# trill-square.net
KiCad netlist of a schematic drawn in EAGLE
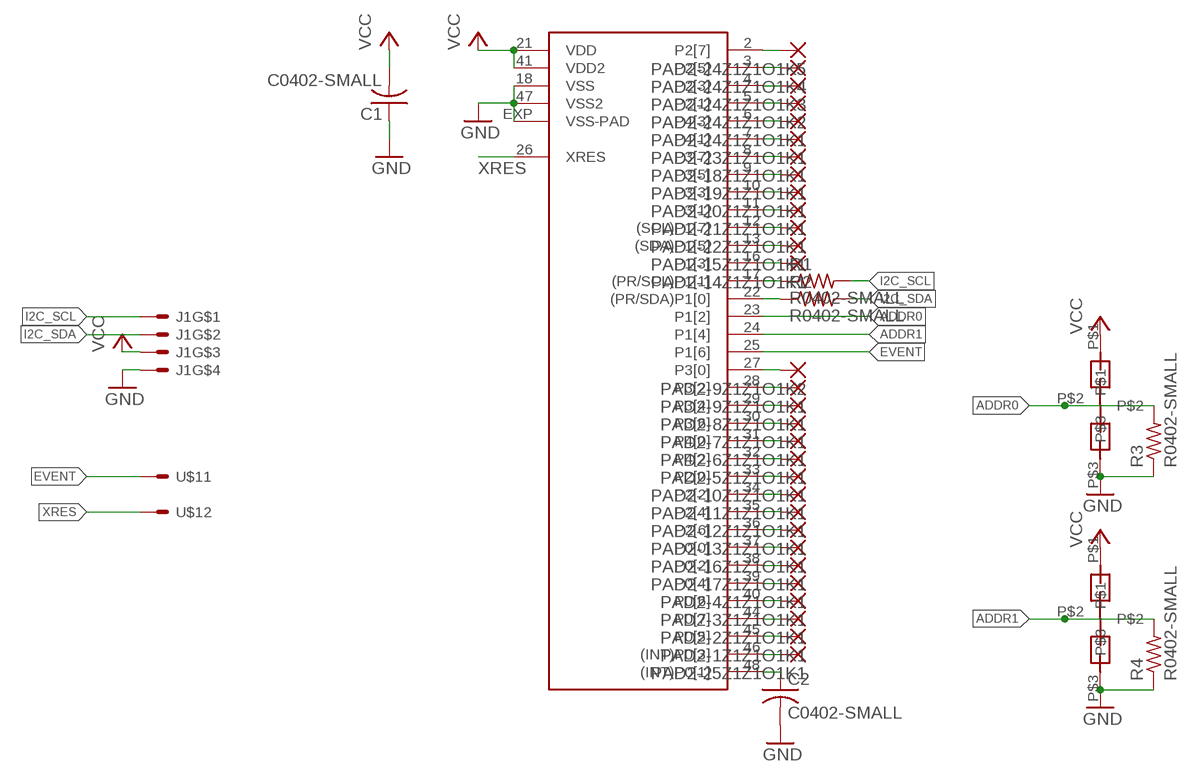
[diagram p0: schematic, sheet 1]

(export (version "E")
  (design (tool "Eeschema 10.0.6"))
  (components
    (comp (ref "C1")
      (value "C0402-SMALL")
      (footprint "eagle-import:C0402-SMALL")
      (libsource (lib "eagle-import") (part "C0402-SMALL"))
    )
    (comp (ref "C2")
      (value "C0402-SMALL")
      (footprint "eagle-import:C0402-SMALL")
      (libsource (lib "eagle-import") (part "C0402-SMALL"))
    )
    (comp (ref "IC1")
      (value "CY8C206X6A")
      (footprint "eagle-import:QFN48-LEADS")
      (libsource (lib "eagle-import") (part "CY8C206X6A"))
    )
    (comp (ref "J1")
      (value "GROVE-SMT")
      (footprint "eagle-import:JST-PH-4-SMT")
      (libsource (lib "eagle-import") (part "GROVE-SMT"))
    )
    (comp (ref "PAD2-1Z1Z1O1K1")
      (value "SMD2")
      (footprint "eagle-import:SMD1,27-2,54")
      (libsource (lib "eagle-import") (part "SMD2"))
    )
    (comp (ref "PAD2-2Z1Z1O1K1")
      (value "SMD2")
      (footprint "eagle-import:SMD1,27-2,54")
      (libsource (lib "eagle-import") (part "SMD2"))
    )
    (comp (ref "PAD2-3Z1Z1O1K1")
      (value "SMD2")
      (footprint "eagle-import:SMD1,27-2,54")
      (libsource (lib "eagle-import") (part "SMD2"))
    )
    (comp (ref "PAD2-4Z1Z1O1K1")
      (value "SMD2")
      (footprint "eagle-import:SMD1,27-2,54")
      (libsource (lib "eagle-import") (part "SMD2"))
    )
    (comp (ref "PAD2-5Z1Z1O1K1")
      (value "SMD2")
      (footprint "eagle-import:SMD1,27-2,54")
      (libsource (lib "eagle-import") (part "SMD2"))
    )
    (comp (ref "PAD2-6Z1Z1O1K1")
      (value "SMD2")
      (footprint "eagle-import:SMD1,27-2,54")
      (libsource (lib "eagle-import") (part "SMD2"))
    )
    (comp (ref "PAD2-7Z1Z1O1K1")
      (value "SMD2")
      (footprint "eagle-import:SMD1,27-2,54")
      (libsource (lib "eagle-import") (part "SMD2"))
    )
    (comp (ref "PAD2-8Z1Z1O1K1")
      (value "SMD2")
      (footprint "eagle-import:SMD1,27-2,54")
      (libsource (lib "eagle-import") (part "SMD2"))
    )
    (comp (ref "PAD2-9Z1Z1O1K1")
      (value "SMD2")
      (footprint "eagle-import:SMD1,27-2,54")
      (libsource (lib "eagle-import") (part "SMD2"))
    )
    (comp (ref "PAD2-9Z1Z1O1K2")
      (value "SMD2")
      (footprint "eagle-import:SMD1,27-2,54")
      (libsource (lib "eagle-import") (part "SMD2"))
    )
    (comp (ref "PAD2-10Z1Z1O1K1")
      (value "SMD2")
      (footprint "eagle-import:SMD1,27-2,54")
      (libsource (lib "eagle-import") (part "SMD2"))
    )
    (comp (ref "PAD2-11Z1Z1O1K1")
      (value "SMD2")
      (footprint "eagle-import:SMD1,27-2,54")
      (libsource (lib "eagle-import") (part "SMD2"))
    )
    (comp (ref "PAD2-12Z1Z1O1K1")
      (value "SMD2")
      (footprint "eagle-import:SMD1,27-2,54")
      (libsource (lib "eagle-import") (part "SMD2"))
    )
    (comp (ref "PAD2-13Z1Z1O1K1")
      (value "SMD2")
      (footprint "eagle-import:SMD1,27-2,54")
      (libsource (lib "eagle-import") (part "SMD2"))
    )
    (comp (ref "PAD2-14Z1Z1O1K1")
      (value "SMD2")
      (footprint "eagle-import:SMD1,27-2,54")
      (libsource (lib "eagle-import") (part "SMD2"))
    )
    (comp (ref "PAD2-15Z1Z1O1K1")
      (value "SMD2")
      (footprint "eagle-import:SMD1,27-2,54")
      (libsource (lib "eagle-import") (part "SMD2"))
    )
    (comp (ref "PAD2-16Z1Z1O1K1")
      (value "SMD2")
      (footprint "eagle-import:SMD1,27-2,54")
      (libsource (lib "eagle-import") (part "SMD2"))
    )
    (comp (ref "PAD2-17Z1Z1O1K1")
      (value "SMD2")
      (footprint "eagle-import:SMD1,27-2,54")
      (libsource (lib "eagle-import") (part "SMD2"))
    )
    (comp (ref "PAD2-18Z1Z1O1K1")
      (value "SMD2")
      (footprint "eagle-import:SMD1,27-2,54")
      (libsource (lib "eagle-import") (part "SMD2"))
    )
    (comp (ref "PAD2-19Z1Z1O1K1")
      (value "SMD2")
      (footprint "eagle-import:SMD1,27-2,54")
      (libsource (lib "eagle-import") (part "SMD2"))
    )
    (comp (ref "PAD2-20Z1Z1O1K1")
      (value "SMD2")
      (footprint "eagle-import:SMD1,27-2,54")
      (libsource (lib "eagle-import") (part "SMD2"))
    )
    (comp (ref "PAD2-21Z1Z1O1K1")
      (value "SMD2")
      (footprint "eagle-import:SMD1,27-2,54")
      (libsource (lib "eagle-import") (part "SMD2"))
    )
    (comp (ref "PAD2-22Z1Z1O1K1")
      (value "SMD2")
      (footprint "eagle-import:SMD1,27-2,54")
      (libsource (lib "eagle-import") (part "SMD2"))
    )
    (comp (ref "PAD2-23Z1Z1O1K1")
      (value "SMD2")
      (footprint "eagle-import:SMD1,27-2,54")
      (libsource (lib "eagle-import") (part "SMD2"))
    )
    (comp (ref "PAD2-24Z1Z1O1K1")
      (value "SMD2")
      (footprint "eagle-import:SMD1,27-2,54")
      (libsource (lib "eagle-import") (part "SMD2"))
    )
    (comp (ref "PAD2-24Z1Z1O1K2")
      (value "SMD2")
      (footprint "eagle-import:SMD1,27-2,54")
      (libsource (lib "eagle-import") (part "SMD2"))
    )
    (comp (ref "PAD2-24Z1Z1O1K3")
      (value "SMD2")
      (footprint "eagle-import:SMD1,27-2,54")
      (libsource (lib "eagle-import") (part "SMD2"))
    )
    (comp (ref "PAD2-24Z1Z1O1K4")
      (value "SMD2")
      (footprint "eagle-import:SMD1,27-2,54")
      (libsource (lib "eagle-import") (part "SMD2"))
    )
    (comp (ref "PAD2-24Z1Z1O1K5")
      (value "SMD2")
      (footprint "eagle-import:SMD1,27-2,54")
      (libsource (lib "eagle-import") (part "SMD2"))
    )
    (comp (ref "PAD2-25Z1Z1O1K1")
      (value "SMD2")
      (footprint "eagle-import:SMD1,27-2,54")
      (libsource (lib "eagle-import") (part "SMD2"))
    )
    (comp (ref "R1")
      (value "R0402-SMALL")
      (footprint "eagle-import:C0402-SMALL")
      (libsource (lib "eagle-import") (part "R0402-SMALL"))
    )
    (comp (ref "R2")
      (value "R0402-SMALL")
      (footprint "eagle-import:C0402-SMALL")
      (libsource (lib "eagle-import") (part "R0402-SMALL"))
    )
    (comp (ref "R3")
      (value "R0402-SMALL")
      (footprint "eagle-import:C0402-SMALL")
      (libsource (lib "eagle-import") (part "R0402-SMALL"))
    )
    (comp (ref "R4")
      (value "R0402-SMALL")
      (footprint "eagle-import:C0402-SMALL")
      (libsource (lib "eagle-import") (part "R0402-SMALL"))
    )
    (comp (ref "U$7")
      (value "SOLDER_JUMPER_3PAD")
      (footprint "eagle-import:SOLDER_JUMPER_3PAD")
      (libsource (lib "eagle-import") (part "SOLDER_JUMPER_3PAD"))
    )
    (comp (ref "U$8")
      (value "SOLDER_JUMPER_3PAD")
      (footprint "eagle-import:SOLDER_JUMPER_3PAD")
      (libsource (lib "eagle-import") (part "SOLDER_JUMPER_3PAD"))
    )
    (comp (ref "U$11")
      (value "JST-SMT-EXTRAPAD")
      (footprint "eagle-import:JST-SMT-EXTRAPAD")
      (libsource (lib "eagle-import") (part "JST-SMT-EXTRAPAD"))
    )
    (comp (ref "U$12")
      (value "JST-SMT-EXTRAPAD")
      (footprint "eagle-import:JST-SMT-EXTRAPAD")
      (libsource (lib "eagle-import") (part "JST-SMT-EXTRAPAD"))
    )
  )
  (nets
    (net (code "1") (name "ADDR0") (class "Default")
      (node (ref "IC1") (pin "23") (pinfunction "P1[2]_23") (pintype "bidirectional"))
      (node (ref "R3") (pin "P$2") (pinfunction "2_P$2") (pintype "passive"))
      (node (ref "U$7") (pin "P$2") (pinfunction "P$2_P$2") (pintype "bidirectional"))
    )
    (net (code "2") (name "ADDR1") (class "Default")
      (node (ref "IC1") (pin "24") (pinfunction "P1[4]_24") (pintype "bidirectional"))
      (node (ref "R4") (pin "P$2") (pinfunction "2_P$2") (pintype "passive"))
      (node (ref "U$8") (pin "P$2") (pinfunction "P$2_P$2") (pintype "bidirectional"))
    )
    (net (code "3") (name "EVENT") (class "Default")
      (node (ref "IC1") (pin "25") (pinfunction "P1[6]_25") (pintype "bidirectional"))
      (node (ref "U$11") (pin "P$1") (pinfunction "S_P$1") (pintype "passive"))
    )
    (net (code "4") (name "GND") (class "Default")
      (node (ref "C1") (pin "P$1") (pinfunction "1_P$1") (pintype "passive"))
      (node (ref "C2") (pin "P$2") (pinfunction "2_P$2") (pintype "passive"))
      (node (ref "IC1") (pin "18") (pinfunction "VSS_18") (pintype "bidirectional"))
      (node (ref "IC1") (pin "47") (pinfunction "VSS2_47") (pintype "bidirectional"))
      (node (ref "IC1") (pin "EXP") (pinfunction "VSS-PAD_EXP") (pintype "bidirectional"))
      (node (ref "J1") (pin "4") (pinfunction "S_4") (pintype "passive"))
      (node (ref "R3") (pin "P$1") (pinfunction "1_P$1") (pintype "passive"))
      (node (ref "R4") (pin "P$1") (pinfunction "1_P$1") (pintype "passive"))
      (node (ref "U$7") (pin "P$3") (pinfunction "P$3_P$3") (pintype "bidirectional"))
      (node (ref "U$8") (pin "P$3") (pinfunction "P$3_P$3") (pintype "bidirectional"))
    )
    (net (code "5") (name "I2C_SCL") (class "Default")
      (node (ref "J1") (pin "1") (pinfunction "S_1") (pintype "passive"))
      (node (ref "R1") (pin "P$2") (pinfunction "2_P$2") (pintype "passive"))
    )
    (net (code "6") (name "I2C_SDA") (class "Default")
      (node (ref "J1") (pin "2") (pinfunction "S_2") (pintype "passive"))
      (node (ref "R2") (pin "P$2") (pinfunction "2_P$2") (pintype "passive"))
    )
    (net (code "7") (name "Net-(C2-1)") (class "Default")
      (node (ref "C2") (pin "P$1") (pinfunction "1_P$1") (pintype "passive"))
      (node (ref "IC1") (pin "48") (pinfunction "(INT)P0[1]_48") (pintype "bidirectional"))
    )
    (net (code "8") (name "Net-(IC1-(INT)P0[3])") (class "Default")
      (node (ref "IC1") (pin "46") (pinfunction "(INT)P0[3]_46") (pintype "bidirectional"))
      (node (ref "PAD2-25Z1Z1O1K1") (pin "1") (pinfunction "P_1") (pintype "passive"))
    )
    (net (code "9") (name "Net-(IC1-(PR{slash}SCL)P1[1])") (class "Default")
      (node (ref "IC1") (pin "17") (pinfunction "(PR/SCL)P1[1]_17") (pintype "bidirectional"))
      (node (ref "R1") (pin "P$1") (pinfunction "1_P$1") (pintype "passive"))
    )
    (net (code "10") (name "Net-(IC1-(PR{slash}SDA)P1[0])") (class "Default")
      (node (ref "IC1") (pin "22") (pinfunction "(PR/SDA)P1[0]_22") (pintype "bidirectional"))
      (node (ref "R2") (pin "P$1") (pinfunction "1_P$1") (pintype "passive"))
    )
    (net (code "11") (name "Net-(IC1-(SCL)P1[7])") (class "Default")
      (node (ref "IC1") (pin "12") (pinfunction "(SCL)P1[7]_12") (pintype "bidirectional"))
      (node (ref "PAD2-22Z1Z1O1K1") (pin "1") (pinfunction "P_1") (pintype "passive"))
    )
    (net (code "12") (name "Net-(IC1-(SDA)P1[5])") (class "Default")
      (node (ref "IC1") (pin "13") (pinfunction "(SDA)P1[5]_13") (pintype "bidirectional"))
      (node (ref "PAD2-15Z1Z1O1K1") (pin "1") (pinfunction "P_1") (pintype "passive"))
    )
    (net (code "13") (name "Net-(IC1-P0[0])") (class "Default")
      (node (ref "IC1") (pin "37") (pinfunction "P0[0]_37") (pintype "bidirectional"))
      (node (ref "PAD2-16Z1Z1O1K1") (pin "1") (pinfunction "P_1") (pintype "passive"))
    )
    (net (code "14") (name "Net-(IC1-P0[2])") (class "Default")
      (node (ref "IC1") (pin "38") (pinfunction "P0[2]_38") (pintype "bidirectional"))
      (node (ref "PAD2-17Z1Z1O1K1") (pin "1") (pinfunction "P_1") (pintype "passive"))
    )
    (net (code "15") (name "Net-(IC1-P0[4])") (class "Default")
      (node (ref "IC1") (pin "39") (pinfunction "P0[4]_39") (pintype "bidirectional"))
      (node (ref "PAD2-4Z1Z1O1K1") (pin "1") (pinfunction "P_1") (pintype "passive"))
    )
    (net (code "16") (name "Net-(IC1-P0[5])") (class "Default")
      (node (ref "IC1") (pin "45") (pinfunction "P0[5]_45") (pintype "bidirectional"))
      (node (ref "PAD2-1Z1Z1O1K1") (pin "1") (pinfunction "P_1") (pintype "passive"))
    )
    (net (code "17") (name "Net-(IC1-P0[6])") (class "Default")
      (node (ref "IC1") (pin "40") (pinfunction "P0[6]_40") (pintype "bidirectional"))
      (node (ref "PAD2-3Z1Z1O1K1") (pin "1") (pinfunction "P_1") (pintype "passive"))
    )
    (net (code "18") (name "Net-(IC1-P0[7])") (class "Default")
      (node (ref "IC1") (pin "44") (pinfunction "P0[7]_44") (pintype "bidirectional"))
      (node (ref "PAD2-2Z1Z1O1K1") (pin "1") (pinfunction "P_1") (pintype "passive"))
    )
    (net (code "19") (name "Net-(IC1-P1[3])") (class "Default")
      (node (ref "IC1") (pin "16") (pinfunction "P1[3]_16") (pintype "bidirectional"))
      (node (ref "PAD2-14Z1Z1O1K1") (pin "1") (pinfunction "P_1") (pintype "passive"))
    )
    (net (code "20") (name "Net-(IC1-P2[0])") (class "Default")
      (node (ref "IC1") (pin "33") (pinfunction "P2[0]_33") (pintype "bidirectional"))
      (node (ref "PAD2-10Z1Z1O1K1") (pin "1") (pinfunction "P_1") (pintype "passive"))
    )
    (net (code "21") (name "Net-(IC1-P2[1])") (class "Default")
      (node (ref "IC1") (pin "5") (pinfunction "P2[1]_5") (pintype "bidirectional"))
      (node (ref "PAD2-24Z1Z1O1K2") (pin "1") (pinfunction "P_1") (pintype "passive"))
    )
    (net (code "22") (name "Net-(IC1-P2[2])") (class "Default")
      (node (ref "IC1") (pin "34") (pinfunction "P2[2]_34") (pintype "bidirectional"))
      (node (ref "PAD2-11Z1Z1O1K1") (pin "1") (pinfunction "P_1") (pintype "passive"))
    )
    (net (code "23") (name "Net-(IC1-P2[3])") (class "Default")
      (node (ref "IC1") (pin "4") (pinfunction "P2[3]_4") (pintype "bidirectional"))
      (node (ref "PAD2-24Z1Z1O1K3") (pin "1") (pinfunction "P_1") (pintype "passive"))
    )
    (net (code "24") (name "Net-(IC1-P2[4])") (class "Default")
      (node (ref "IC1") (pin "35") (pinfunction "P2[4]_35") (pintype "bidirectional"))
      (node (ref "PAD2-12Z1Z1O1K1") (pin "1") (pinfunction "P_1") (pintype "passive"))
    )
    (net (code "25") (name "Net-(IC1-P2[5])") (class "Default")
      (node (ref "IC1") (pin "3") (pinfunction "P2[5]_3") (pintype "bidirectional"))
      (node (ref "PAD2-24Z1Z1O1K4") (pin "1") (pinfunction "P_1") (pintype "passive"))
    )
    (net (code "26") (name "Net-(IC1-P2[6])") (class "Default")
      (node (ref "IC1") (pin "36") (pinfunction "P2[6]_36") (pintype "bidirectional"))
      (node (ref "PAD2-13Z1Z1O1K1") (pin "1") (pinfunction "P_1") (pintype "passive"))
    )
    (net (code "27") (name "Net-(IC1-P2[7])") (class "Default")
      (node (ref "IC1") (pin "2") (pinfunction "P2[7]_2") (pintype "bidirectional"))
      (node (ref "PAD2-24Z1Z1O1K5") (pin "1") (pinfunction "P_1") (pintype "passive"))
    )
    (net (code "28") (name "Net-(IC1-P3[0])") (class "Default")
      (node (ref "IC1") (pin "27") (pinfunction "P3[0]_27") (pintype "bidirectional"))
      (node (ref "PAD2-9Z1Z1O1K2") (pin "1") (pinfunction "P_1") (pintype "passive"))
    )
    (net (code "29") (name "Net-(IC1-P3[1])") (class "Default")
      (node (ref "IC1") (pin "11") (pinfunction "P3[1]_11") (pintype "bidirectional"))
      (node (ref "PAD2-21Z1Z1O1K1") (pin "1") (pinfunction "P_1") (pintype "passive"))
    )
    (net (code "30") (name "Net-(IC1-P3[2])") (class "Default")
      (node (ref "IC1") (pin "28") (pinfunction "P3[2]_28") (pintype "bidirectional"))
      (node (ref "PAD2-9Z1Z1O1K1") (pin "1") (pinfunction "P_1") (pintype "passive"))
    )
    (net (code "31") (name "Net-(IC1-P3[3])") (class "Default")
      (node (ref "IC1") (pin "10") (pinfunction "P3[3]_10") (pintype "bidirectional"))
      (node (ref "PAD2-20Z1Z1O1K1") (pin "1") (pinfunction "P_1") (pintype "passive"))
    )
    (net (code "32") (name "Net-(IC1-P3[4])") (class "Default")
      (node (ref "IC1") (pin "29") (pinfunction "P3[4]_29") (pintype "bidirectional"))
      (node (ref "PAD2-8Z1Z1O1K1") (pin "1") (pinfunction "P_1") (pintype "passive"))
    )
    (net (code "33") (name "Net-(IC1-P3[5])") (class "Default")
      (node (ref "IC1") (pin "9") (pinfunction "P3[5]_9") (pintype "bidirectional"))
      (node (ref "PAD2-19Z1Z1O1K1") (pin "1") (pinfunction "P_1") (pintype "passive"))
    )
    (net (code "34") (name "Net-(IC1-P3[6])") (class "Default")
      (node (ref "IC1") (pin "30") (pinfunction "P3[6]_30") (pintype "bidirectional"))
      (node (ref "PAD2-7Z1Z1O1K1") (pin "1") (pinfunction "P_1") (pintype "passive"))
    )
    (net (code "35") (name "Net-(IC1-P3[7])") (class "Default")
      (node (ref "IC1") (pin "8") (pinfunction "P3[7]_8") (pintype "bidirectional"))
      (node (ref "PAD2-18Z1Z1O1K1") (pin "1") (pinfunction "P_1") (pintype "passive"))
    )
    (net (code "36") (name "Net-(IC1-P4[0])") (class "Default")
      (node (ref "IC1") (pin "31") (pinfunction "P4[0]_31") (pintype "bidirectional"))
      (node (ref "PAD2-6Z1Z1O1K1") (pin "1") (pinfunction "P_1") (pintype "passive"))
    )
    (net (code "37") (name "Net-(IC1-P4[1])") (class "Default")
      (node (ref "IC1") (pin "7") (pinfunction "P4[1]_7") (pintype "bidirectional"))
      (node (ref "PAD2-23Z1Z1O1K1") (pin "1") (pinfunction "P_1") (pintype "passive"))
    )
    (net (code "38") (name "Net-(IC1-P4[2])") (class "Default")
      (node (ref "IC1") (pin "32") (pinfunction "P4[2]_32") (pintype "bidirectional"))
      (node (ref "PAD2-5Z1Z1O1K1") (pin "1") (pinfunction "P_1") (pintype "passive"))
    )
    (net (code "39") (name "Net-(IC1-P4[3])") (class "Default")
      (node (ref "IC1") (pin "6") (pinfunction "P4[3]_6") (pintype "bidirectional"))
      (node (ref "PAD2-24Z1Z1O1K1") (pin "1") (pinfunction "P_1") (pintype "passive"))
    )
    (net (code "40") (name "VCC") (class "Default")
      (node (ref "C1") (pin "P$2") (pinfunction "2_P$2") (pintype "passive"))
      (node (ref "IC1") (pin "21") (pinfunction "VDD_21") (pintype "bidirectional"))
      (node (ref "IC1") (pin "41") (pinfunction "VDD2_41") (pintype "bidirectional"))
      (node (ref "J1") (pin "3") (pinfunction "S_3") (pintype "passive"))
      (node (ref "U$7") (pin "P$1") (pinfunction "P$1_P$1") (pintype "bidirectional"))
      (node (ref "U$8") (pin "P$1") (pinfunction "P$1_P$1") (pintype "bidirectional"))
    )
    (net (code "41") (name "XRES") (class "Default")
      (node (ref "IC1") (pin "26") (pinfunction "XRES_26") (pintype "bidirectional"))
      (node (ref "U$12") (pin "P$1") (pinfunction "S_P$1") (pintype "passive"))
    )
  )
)
